# design.net
KiCad netlist of a schematic drawn in EasyEDA Pro
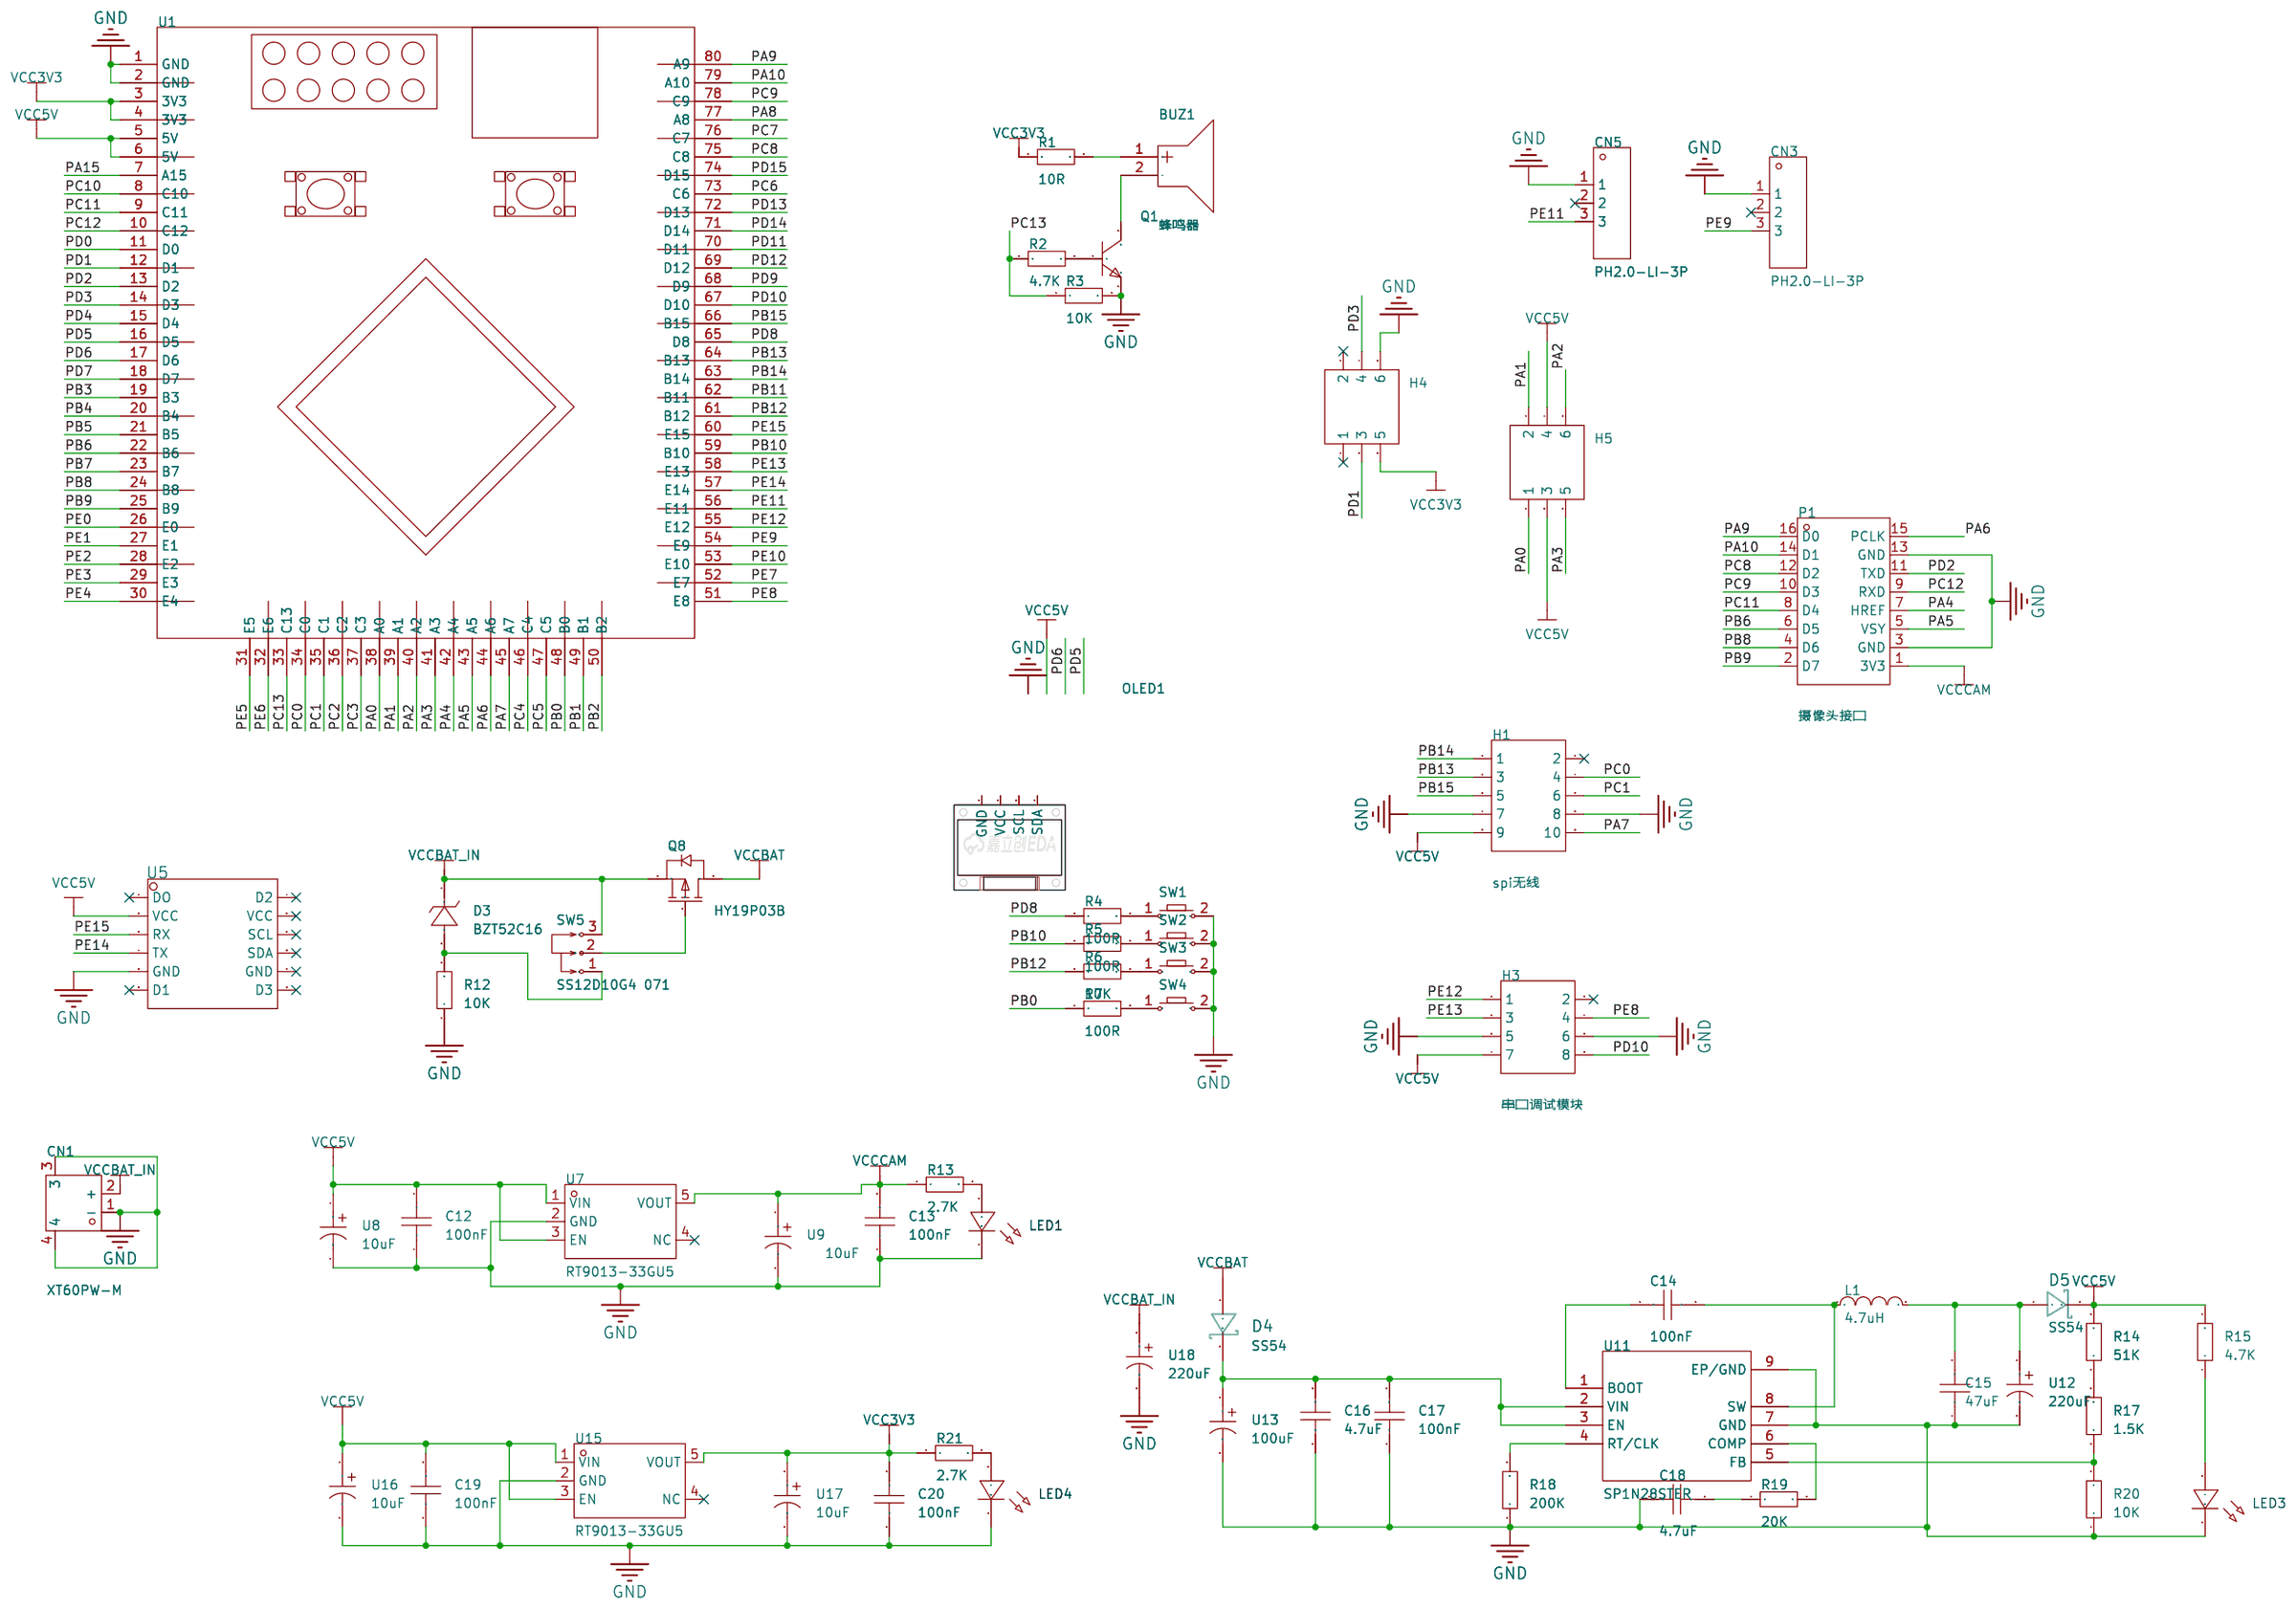
[diagram p0: schematic sheet]

(export (version "E")
  (design (tool "Eeschema 10.0.6"))
  (components
    (comp (ref "BUZ1")
      (value "蜂鸣器")
      (footprint "easyedapro:BUZ-TH_BD9.0-P5.00-D0.6-FD")
      (libsource (lib "easyedapro") (part "蜂鸣器"))
    )
    (comp (ref "C12")
      (value "100nF")
      (footprint "easyedapro:C0603")
      (libsource (lib "easyedapro") (part "CapAcitance"))
    )
    (comp (ref "C13")
      (value "100nF")
      (footprint "easyedapro:C0603")
      (libsource (lib "easyedapro") (part "CapAcitance"))
    )
    (comp (ref "C14")
      (value "100nF")
      (footprint "easyedapro:C0603")
      (libsource (lib "easyedapro") (part "CapAcitance"))
    )
    (comp (ref "C15")
      (value "47uF")
      (footprint "easyedapro:C0603")
      (libsource (lib "easyedapro") (part "CapAcitance"))
    )
    (comp (ref "C16")
      (value "4.7uF")
      (footprint "easyedapro:C0603")
      (libsource (lib "easyedapro") (part "CapAcitance"))
    )
    (comp (ref "C17")
      (value "100nF")
      (footprint "easyedapro:C0603")
      (libsource (lib "easyedapro") (part "CapAcitance"))
    )
    (comp (ref "C18")
      (value "4.7uF")
      (footprint "easyedapro:C0603")
      (libsource (lib "easyedapro") (part "CapAcitance"))
    )
    (comp (ref "C19")
      (value "100nF")
      (footprint "easyedapro:C0603")
      (libsource (lib "easyedapro") (part "CapAcitance"))
    )
    (comp (ref "C20")
      (value "100nF")
      (footprint "easyedapro:C0603")
      (libsource (lib "easyedapro") (part "CapAcitance"))
    )
    (comp (ref "CN1")
      (value "XT60PW-M")
      (footprint "easyedapro:CONN-TH_XT60PW-M")
      (description "类别:-;类型1:-;")
      (fields (field (name "Manufacturer") "AMASS(艾迈斯)"))
      (libsource (lib "easyedapro") (part "XT60PW-M"))
    )
    (comp (ref "CN3")
      (value "PH2.0-LI-3P")
      (footprint "easyedapro:CONN-TH_3P-P2.00_HX20007-3A")
      (libsource (lib "easyedapro") (part "PH2.0-LI-3P"))
    )
    (comp (ref "CN5")
      (value "PH2.0-LI-3P")
      (footprint "easyedapro:CONN-TH_3P-P2.00_HX20007-3A")
      (libsource (lib "easyedapro") (part "PH2.0-LI-3P"))
    )
    (comp (ref "D3")
      (value "BZT52C16")
      (footprint "easyedapro:SOD-123_L2.7-W1.6-LS3.7-RD")
      (description "稳压值(标称值):-;功率:500mW;精度:-;")
      (fields (field (name "Manufacturer") "Slkor(萨科微)"))
      (libsource (lib "easyedapro") (part "BZT52C16_C707145"))
    )
    (comp (ref "D4")
      (value "SS54")
      (footprint "easyedapro:SMA_L4.4-W2.8-LS5.4-R-RD")
      (fields (field (name "Manufacturer") "MDD"))
      (libsource (lib "easyedapro") (part "SS54"))
    )
    (comp (ref "D5")
      (value "SS54")
      (footprint "easyedapro:SMA_L4.4-W2.8-LS5.4-R-RD")
      (fields (field (name "Manufacturer") "MDD"))
      (libsource (lib "easyedapro") (part "SS54"))
    )
    (comp (ref "H1")
      (value "spi无线")
      (footprint "easyedapro:HDR-TH_10P-P2.54-V-F-R2-C5-S2.54")
      (libsource (lib "easyedapro") (part "HDR-F-2.54_2x5"))
    )
    (comp (ref "H3")
      (value "串口调试模块")
      (footprint "easyedapro:HDR-TH_8P-P2.54-V-F-R2-C4-S2.54-1")
      (libsource (lib "easyedapro") (part "HDR-F-2.54_2x4"))
    )
    (comp (ref "H4")
      (value "~")
      (footprint "easyedapro:HDR-TH_6P-P2.54-V-F-R2-C3-S2.54")
      (libsource (lib "easyedapro") (part "HDR-F-2.54_2x3"))
    )
    (comp (ref "H5")
      (value "~")
      (footprint "easyedapro:HDR-TH_6P-P2.54-V-F-R2-C3-S2.54")
      (libsource (lib "easyedapro") (part "HDR-F-2.54_2x3"))
    )
    (comp (ref "L1")
      (value "4.7uH")
      (footprint "easyedapro:L0603")
      (libsource (lib "easyedapro") (part "SDFL1608S100KTF"))
    )
    (comp (ref "LED1")
      (value "~")
      (footprint "easyedapro:LED_0603")
      (libsource (lib "easyedapro") (part "LED_G"))
    )
    (comp (ref "LED3")
      (value "~")
      (footprint "easyedapro:LED_0603")
      (libsource (lib "easyedapro") (part "LED_G"))
    )
    (comp (ref "LED4")
      (value "~")
      (footprint "easyedapro:LED_0603")
      (libsource (lib "easyedapro") (part "LED_G"))
    )
    (comp (ref "OLED1")
      (value "~")
      (footprint "easyedapro:0.96OLED_4P")
      (libsource (lib "easyedapro") (part "0.96OLED模块_4P"))
    )
    (comp (ref "P1")
      (value "摄像头接口")
      (footprint "easyedapro:总钻风摄像头接口")
      (libsource (lib "easyedapro") (part "总钻风"))
    )
    (comp (ref "Q1")
      (value "~")
      (footprint "easyedapro:S8050_SOT-23")
      (libsource (lib "easyedapro") (part "NPN"))
    )
    (comp (ref "Q8")
      (value "HY19P03B")
      (footprint "easyedapro:TO-263-2_L10.2-W8.7-P5.08-LS15.1-BR")
      (fields (field (name "Manufacturer") "HUAYI(华羿微)"))
      (libsource (lib "easyedapro") (part "HY19P03B_C410273"))
    )
    (comp (ref "R1") (value "10R") (footprint "easyedapro:R0603") (libsource (lib "easyedapro") (part "电阻")))
    (comp (ref "R2") (value "4.7K") (footprint "easyedapro:R0603") (libsource (lib "easyedapro") (part "电阻")))
    (comp (ref "R3") (value "10K") (footprint "easyedapro:R0603") (libsource (lib "easyedapro") (part "电阻")))
    (comp (ref "R4") (value "10K") (footprint "easyedapro:R0603") (libsource (lib "easyedapro") (part "电阻")))
    (comp (ref "R5") (value "10K") (footprint "easyedapro:R0603") (libsource (lib "easyedapro") (part "电阻")))
    (comp (ref "R6") (value "10K") (footprint "easyedapro:R0603") (libsource (lib "easyedapro") (part "电阻")))
    (comp (ref "R7") (value "10K") (footprint "easyedapro:R0603") (libsource (lib "easyedapro") (part "电阻")))
    (comp (ref "R12") (value "10K") (footprint "easyedapro:R0603") (libsource (lib "easyedapro") (part "电阻")))
    (comp (ref "R13")
      (value "2.7K")
      (footprint "easyedapro:R0603")
      (libsource (lib "easyedapro") (part "电阻"))
    )
    (comp (ref "R14") (value "51K") (footprint "easyedapro:R0603") (libsource (lib "easyedapro") (part "电阻")))
    (comp (ref "R15")
      (value "4.7K")
      (footprint "easyedapro:R0603")
      (libsource (lib "easyedapro") (part "电阻"))
    )
    (comp (ref "R17")
      (value "1.5K")
      (footprint "easyedapro:R0603")
      (libsource (lib "easyedapro") (part "电阻"))
    )
    (comp (ref "R18")
      (value "200K")
      (footprint "easyedapro:R0603")
      (libsource (lib "easyedapro") (part "电阻"))
    )
    (comp (ref "R19") (value "20K") (footprint "easyedapro:R0603") (libsource (lib "easyedapro") (part "电阻")))
    (comp (ref "R20") (value "10K") (footprint "easyedapro:R0603") (libsource (lib "easyedapro") (part "电阻")))
    (comp (ref "R21")
      (value "2.7K")
      (footprint "easyedapro:R0603")
      (libsource (lib "easyedapro") (part "电阻"))
    )
    (comp (ref "SW1")
      (value "~")
      (footprint "easyedapro:Key_SMD_3x4x2")
      (libsource (lib "easyedapro") (part "轻触按键x2"))
    )
    (comp (ref "SW2")
      (value "~")
      (footprint "easyedapro:Key_SMD_3x4x2")
      (libsource (lib "easyedapro") (part "轻触按键x2"))
    )
    (comp (ref "SW3")
      (value "~")
      (footprint "easyedapro:Key_SMD_3x4x2")
      (libsource (lib "easyedapro") (part "轻触按键x2"))
    )
    (comp (ref "SW4")
      (value "~")
      (footprint "easyedapro:Key_SMD_3x4x2")
      (libsource (lib "easyedapro") (part "轻触按键x2"))
    )
    (comp (ref "SW5")
      (value "SS12D10G4 071")
      (footprint "easyedapro:SW-TH_SHOU-HAN_SS12D10G4")
      (description "电路结构:单刀双掷;安装方式:直插;开关颜色:-;额定电流(DC):2A;额定电压(DC):125V;额定电流(AC):-;额定电压(AC):-;机械寿命:3千次;")
      (fields (field (name "Manufacturer") "SHOU HAN(首韩)"))
      (libsource (lib "easyedapro") (part "SS12D10G4 071"))
    )
    (comp (ref "U1")
      (value "~")
      (footprint "easyedapro:CH32V307VCT6核心板")
      (libsource (lib "easyedapro") (part "CH32V307VCT6"))
    )
    (comp (ref "U5")
      (value "~")
      (footprint "easyedapro:维特智能JY901S")
      (description "9轴姿态角度传感器")
      (libsource (lib "easyedapro") (part "维特智能JY901S"))
    )
    (comp (ref "U7")
      (value "RT9013-33GU5")
      (footprint "easyedapro:SC-70-5_L2.0-W1.3-P0.65-LS2.1-BR")
      (description "输出类型:固定;最大输入电压:5.5V;输出电压:3.3V;最大输出电流:500mA;电源纹波抑制比(PSRR):50dB@(10kHz);输出极性:正极;")
      (fields (field (name "Manufacturer") "RICHTEK(立锜)"))
      (libsource (lib "easyedapro") (part "RT9013-33GU5"))
    )
    (comp (ref "U8")
      (value "10uF")
      (footprint "easyedapro:CAP-SMD_L7.3-W4.3-FD")
      (description "容值:470uF;精度:±20%;额定电压:10V;等效串联电阻:50mΩ@100kHZ;")
      (fields
        (field (name "Manufacturer Part") "TPSE477M010R0050")
        (field (name "Manufacturer") "Kyocera AVX")
      )
      (libsource (lib "easyedapro") (part "TPSE477M010R0050"))
    )
    (comp (ref "U9")
      (value "10uF")
      (footprint "easyedapro:CAP-SMD_L7.3-W4.3-FD")
      (description "容值:470uF;精度:±20%;额定电压:10V;等效串联电阻:50mΩ@100kHZ;")
      (fields
        (field (name "Manufacturer Part") "TPSE477M010R0050")
        (field (name "Manufacturer") "Kyocera AVX")
      )
      (libsource (lib "easyedapro") (part "TPSE477M010R0050"))
    )
    (comp (ref "U11")
      (value "SP1N28STER")
      (footprint "easyedapro:ESOP-8_L4.9-W3.9-P1.27-LS6.0-TL-EP")
      (fields (field (name "Manufacturer Part") "TPS5430DDAR") (field (name "Manufacturer") "TI(德州仪器)"))
      (libsource (lib "easyedapro") (part "SP1N28STER"))
    )
    (comp (ref "U12")
      (value "220uF")
      (footprint "easyedapro:CAP-SMD_L7.3-W4.3-FD")
      (description "容值:470uF;精度:±20%;额定电压:10V;等效串联电阻:50mΩ@100kHZ;")
      (fields
        (field (name "Manufacturer Part") "TPSE477M010R0050")
        (field (name "Manufacturer") "Kyocera AVX")
      )
      (libsource (lib "easyedapro") (part "TPSE477M010R0050"))
    )
    (comp (ref "U13")
      (value "100uF")
      (footprint "easyedapro:CAP-SMD_L7.3-W4.3-FD")
      (description "容值:470uF;精度:±20%;额定电压:10V;等效串联电阻:50mΩ@100kHZ;")
      (fields
        (field (name "Manufacturer Part") "TPSE477M010R0050")
        (field (name "Manufacturer") "Kyocera AVX")
      )
      (libsource (lib "easyedapro") (part "TPSE477M010R0050"))
    )
    (comp (ref "U15")
      (value "RT9013-33GU5")
      (footprint "easyedapro:SC-70-5_L2.0-W1.3-P0.65-LS2.1-BR")
      (description "输出类型:固定;最大输入电压:5.5V;输出电压:3.3V;最大输出电流:500mA;电源纹波抑制比(PSRR):50dB@(10kHz);输出极性:正极;")
      (fields (field (name "Manufacturer") "RICHTEK(立锜)"))
      (libsource (lib "easyedapro") (part "RT9013-33GU5"))
    )
    (comp (ref "U16")
      (value "10uF")
      (footprint "easyedapro:CAP-SMD_L7.3-W4.3-FD")
      (description "容值:470uF;精度:±20%;额定电压:10V;等效串联电阻:50mΩ@100kHZ;")
      (fields
        (field (name "Manufacturer Part") "TPSE477M010R0050")
        (field (name "Manufacturer") "Kyocera AVX")
      )
      (libsource (lib "easyedapro") (part "TPSE477M010R0050"))
    )
    (comp (ref "U17")
      (value "10uF")
      (footprint "easyedapro:CAP-SMD_L7.3-W4.3-FD")
      (description "容值:470uF;精度:±20%;额定电压:10V;等效串联电阻:50mΩ@100kHZ;")
      (fields
        (field (name "Manufacturer Part") "TPSE477M010R0050")
        (field (name "Manufacturer") "Kyocera AVX")
      )
      (libsource (lib "easyedapro") (part "TPSE477M010R0050"))
    )
    (comp (ref "U18")
      (value "220uF")
      (footprint "easyedapro:CAP-SMD_L7.3-W4.3-FD")
      (description "容值:470uF;精度:±20%;额定电压:10V;等效串联电阻:50mΩ@100kHZ;")
      (fields
        (field (name "Manufacturer Part") "TPSE477M010R0050")
        (field (name "Manufacturer") "Kyocera AVX")
      )
      (libsource (lib "easyedapro") (part "TPSE477M010R0050"))
    )
  )
  (nets
    (net (code "1") (name "/PA0") (class "Default")
      (node (ref "H5") (pin "1") (pinfunction "1_1") (pintype "input"))
      (node (ref "U1") (pin "38") (pinfunction "A0_38") (pintype "input"))
    )
    (net (code "2") (name "/PA1") (class "Default")
      (node (ref "H5") (pin "2") (pinfunction "2_2") (pintype "input"))
      (node (ref "U1") (pin "39") (pinfunction "A1_39") (pintype "input"))
    )
    (net (code "3") (name "/PA2") (class "Default")
      (node (ref "H5") (pin "6") (pinfunction "6_6") (pintype "input"))
      (node (ref "U1") (pin "40") (pinfunction "A2_40") (pintype "input"))
    )
    (net (code "4") (name "/PA3") (class "Default")
      (node (ref "H5") (pin "5") (pinfunction "5_5") (pintype "input"))
      (node (ref "U1") (pin "41") (pinfunction "A3_41") (pintype "input"))
    )
    (net (code "5") (name "/PA4") (class "Default")
      (node (ref "P1") (pin "7") (pinfunction "HREF_7") (pintype "input"))
      (node (ref "U1") (pin "42") (pinfunction "A4_42") (pintype "input"))
    )
    (net (code "6") (name "/PA5") (class "Default")
      (node (ref "P1") (pin "5") (pinfunction "VSY_5") (pintype "input"))
      (node (ref "U1") (pin "43") (pinfunction "A5_43") (pintype "input"))
    )
    (net (code "7") (name "/PA6") (class "Default")
      (node (ref "P1") (pin "15") (pinfunction "PCLK_15") (pintype "input"))
      (node (ref "U1") (pin "44") (pinfunction "A6_44") (pintype "input"))
    )
    (net (code "8") (name "/PA7") (class "Default")
      (node (ref "H1") (pin "10") (pinfunction "10_10") (pintype "input"))
      (node (ref "U1") (pin "45") (pinfunction "A7_45") (pintype "input"))
    )
    (net (code "9") (name "/PA8") (class "Default")
      (node (ref "U1") (pin "77") (pinfunction "A8_77") (pintype "input"))
    )
    (net (code "10") (name "/PA9") (class "Default")
      (node (ref "P1") (pin "16") (pinfunction "D0_16") (pintype "input"))
      (node (ref "U1") (pin "80") (pinfunction "A9_80") (pintype "input"))
    )
    (net (code "11") (name "/PA10") (class "Default")
      (node (ref "P1") (pin "14") (pinfunction "D1_14") (pintype "input"))
      (node (ref "U1") (pin "79") (pinfunction "A10_79") (pintype "input"))
    )
    (net (code "12") (name "/PA15") (class "Default")
      (node (ref "U1") (pin "7") (pinfunction "A15_7") (pintype "input"))
    )
    (net (code "13") (name "/PB0") (class "Default")
      (node (ref "R7") (pin "1") (pinfunction "1_1") (pintype "input"))
      (node (ref "U1") (pin "48") (pinfunction "B0_48") (pintype "input"))
    )
    (net (code "14") (name "/PB1") (class "Default")
      (node (ref "U1") (pin "49") (pinfunction "B1_49") (pintype "input"))
    )
    (net (code "15") (name "/PB2") (class "Default")
      (node (ref "U1") (pin "50") (pinfunction "B2_50") (pintype "input"))
    )
    (net (code "16") (name "/PB3") (class "Default")
      (node (ref "U1") (pin "19") (pinfunction "B3_19") (pintype "input"))
    )
    (net (code "17") (name "/PB4") (class "Default")
      (node (ref "U1") (pin "20") (pinfunction "B4_20") (pintype "input"))
    )
    (net (code "18") (name "/PB5") (class "Default")
      (node (ref "U1") (pin "21") (pinfunction "B5_21") (pintype "input"))
    )
    (net (code "19") (name "/PB6") (class "Default")
      (node (ref "P1") (pin "6") (pinfunction "D5_6") (pintype "input"))
      (node (ref "U1") (pin "22") (pinfunction "B6_22") (pintype "input"))
    )
    (net (code "20") (name "/PB7") (class "Default")
      (node (ref "U1") (pin "23") (pinfunction "B7_23") (pintype "input"))
    )
    (net (code "21") (name "/PB8") (class "Default")
      (node (ref "P1") (pin "4") (pinfunction "D6_4") (pintype "input"))
      (node (ref "U1") (pin "24") (pinfunction "B8_24") (pintype "input"))
    )
    (net (code "22") (name "/PB9") (class "Default")
      (node (ref "P1") (pin "2") (pinfunction "D7_2") (pintype "input"))
      (node (ref "U1") (pin "25") (pinfunction "B9_25") (pintype "input"))
    )
    (net (code "23") (name "/PB10") (class "Default")
      (node (ref "R5") (pin "1") (pinfunction "1_1") (pintype "input"))
      (node (ref "U1") (pin "59") (pinfunction "B10_59") (pintype "input"))
    )
    (net (code "24") (name "/PB11") (class "Default")
      (node (ref "U1") (pin "62") (pinfunction "B11_62") (pintype "input"))
    )
    (net (code "25") (name "/PB12") (class "Default")
      (node (ref "R6") (pin "1") (pinfunction "1_1") (pintype "input"))
      (node (ref "U1") (pin "61") (pinfunction "B12_61") (pintype "input"))
    )
    (net (code "26") (name "/PB13") (class "Default")
      (node (ref "H1") (pin "3") (pinfunction "3_3") (pintype "input"))
      (node (ref "U1") (pin "64") (pinfunction "B13_64") (pintype "input"))
    )
    (net (code "27") (name "/PB14") (class "Default")
      (node (ref "H1") (pin "1") (pinfunction "1_1") (pintype "input"))
      (node (ref "U1") (pin "63") (pinfunction "B14_63") (pintype "input"))
    )
    (net (code "28") (name "/PB15") (class "Default")
      (node (ref "H1") (pin "5") (pinfunction "5_5") (pintype "input"))
      (node (ref "U1") (pin "66") (pinfunction "B15_66") (pintype "input"))
    )
    (net (code "29") (name "/PC0") (class "Default")
      (node (ref "H1") (pin "4") (pinfunction "4_4") (pintype "input"))
      (node (ref "U1") (pin "34") (pinfunction "C0_34") (pintype "input"))
    )
    (net (code "30") (name "/PC1") (class "Default")
      (node (ref "H1") (pin "6") (pinfunction "6_6") (pintype "input"))
      (node (ref "U1") (pin "35") (pinfunction "C1_35") (pintype "input"))
    )
    (net (code "31") (name "/PC2") (class "Default")
      (node (ref "U1") (pin "36") (pinfunction "C2_36") (pintype "input"))
    )
    (net (code "32") (name "/PC3") (class "Default")
      (node (ref "U1") (pin "37") (pinfunction "C3_37") (pintype "input"))
    )
    (net (code "33") (name "/PC4") (class "Default")
      (node (ref "U1") (pin "46") (pinfunction "C4_46") (pintype "input"))
    )
    (net (code "34") (name "/PC5") (class "Default")
      (node (ref "U1") (pin "47") (pinfunction "C5_47") (pintype "input"))
    )
    (net (code "35") (name "/PC6") (class "Default")
      (node (ref "U1") (pin "73") (pinfunction "C6_73") (pintype "input"))
    )
    (net (code "36") (name "/PC7") (class "Default")
      (node (ref "U1") (pin "76") (pinfunction "C7_76") (pintype "input"))
    )
    (net (code "37") (name "/PC8") (class "Default")
      (node (ref "P1") (pin "12") (pinfunction "D2_12") (pintype "input"))
      (node (ref "U1") (pin "75") (pinfunction "C8_75") (pintype "input"))
    )
    (net (code "38") (name "/PC9") (class "Default")
      (node (ref "P1") (pin "10") (pinfunction "D3_10") (pintype "input"))
      (node (ref "U1") (pin "78") (pinfunction "C9_78") (pintype "input"))
    )
    (net (code "39") (name "/PC10") (class "Default")
      (node (ref "U1") (pin "8") (pinfunction "C10_8") (pintype "input"))
    )
    (net (code "40") (name "/PC11") (class "Default")
      (node (ref "P1") (pin "8") (pinfunction "D4_8") (pintype "input"))
      (node (ref "U1") (pin "9") (pinfunction "C11_9") (pintype "input"))
    )
    (net (code "41") (name "/PC12") (class "Default")
      (node (ref "P1") (pin "9") (pinfunction "RXD_9") (pintype "input"))
      (node (ref "U1") (pin "10") (pinfunction "C12_10") (pintype "input"))
    )
    (net (code "42") (name "/PC13") (class "Default")
      (node (ref "R2") (pin "1") (pinfunction "1_1") (pintype "input"))
      (node (ref "R3") (pin "1") (pinfunction "1_1") (pintype "input"))
      (node (ref "U1") (pin "33") (pinfunction "C13_33") (pintype "input"))
    )
    (net (code "43") (name "/PD0") (class "Default")
      (node (ref "U1") (pin "11") (pinfunction "D0_11") (pintype "input"))
    )
    (net (code "44") (name "/PD1") (class "Default")
      (node (ref "H4") (pin "3") (pinfunction "3_3") (pintype "input"))
      (node (ref "U1") (pin "12") (pinfunction "D1_12") (pintype "input"))
    )
    (net (code "45") (name "/PD2") (class "Default")
      (node (ref "P1") (pin "11") (pinfunction "TXD_11") (pintype "input"))
      (node (ref "U1") (pin "13") (pinfunction "D2_13") (pintype "input"))
    )
    (net (code "46") (name "/PD3") (class "Default")
      (node (ref "H4") (pin "4") (pinfunction "4_4") (pintype "input"))
      (node (ref "U1") (pin "14") (pinfunction "D3_14") (pintype "input"))
    )
    (net (code "47") (name "/PD4") (class "Default")
      (node (ref "U1") (pin "15") (pinfunction "D4_15") (pintype "input"))
    )
    (net (code "48") (name "/PD5") (class "Default")
      (node (ref "U1") (pin "16") (pinfunction "D5_16") (pintype "input"))
    )
    (net (code "49") (name "/PD6") (class "Default")
      (node (ref "U1") (pin "17") (pinfunction "D6_17") (pintype "input"))
    )
    (net (code "50") (name "/PD7") (class "Default")
      (node (ref "U1") (pin "18") (pinfunction "D7_18") (pintype "input"))
    )
    (net (code "51") (name "/PD8") (class "Default")
      (node (ref "R4") (pin "1") (pinfunction "1_1") (pintype "input"))
      (node (ref "U1") (pin "65") (pinfunction "D8_65") (pintype "input"))
    )
    (net (code "52") (name "/PD9") (class "Default")
      (node (ref "U1") (pin "68") (pinfunction "D9_68") (pintype "input"))
    )
    (net (code "53") (name "/PD10") (class "Default")
      (node (ref "H3") (pin "8") (pinfunction "8_8") (pintype "input"))
      (node (ref "U1") (pin "67") (pinfunction "D10_67") (pintype "input"))
    )
    (net (code "54") (name "/PD11") (class "Default")
      (node (ref "U1") (pin "70") (pinfunction "D11_70") (pintype "input"))
    )
    (net (code "55") (name "/PD12") (class "Default")
      (node (ref "U1") (pin "69") (pinfunction "D12_69") (pintype "input"))
    )
    (net (code "56") (name "/PD13") (class "Default")
      (node (ref "U1") (pin "72") (pinfunction "D13_72") (pintype "input"))
    )
    (net (code "57") (name "/PD14") (class "Default")
      (node (ref "U1") (pin "71") (pinfunction "D14_71") (pintype "input"))
    )
    (net (code "58") (name "/PD15") (class "Default")
      (node (ref "U1") (pin "74") (pinfunction "D15_74") (pintype "input"))
    )
    (net (code "59") (name "/PE0") (class "Default")
      (node (ref "U1") (pin "26") (pinfunction "E0_26") (pintype "input"))
    )
    (net (code "60") (name "/PE1") (class "Default")
      (node (ref "U1") (pin "27") (pinfunction "E1_27") (pintype "input"))
    )
    (net (code "61") (name "/PE2") (class "Default")
      (node (ref "U1") (pin "28") (pinfunction "E2_28") (pintype "input"))
    )
    (net (code "62") (name "/PE3") (class "Default")
      (node (ref "U1") (pin "29") (pinfunction "E3_29") (pintype "input"))
    )
    (net (code "63") (name "/PE4") (class "Default")
      (node (ref "U1") (pin "30") (pinfunction "E4_30") (pintype "input"))
    )
    (net (code "64") (name "/PE5") (class "Default")
      (node (ref "U1") (pin "31") (pinfunction "E5_31") (pintype "input"))
    )
    (net (code "65") (name "/PE6") (class "Default")
      (node (ref "U1") (pin "32") (pinfunction "E6_32") (pintype "input"))
    )
    (net (code "66") (name "/PE7") (class "Default")
      (node (ref "U1") (pin "52") (pinfunction "E7_52") (pintype "input"))
    )
    (net (code "67") (name "/PE8") (class "Default")
      (node (ref "H3") (pin "4") (pinfunction "4_4") (pintype "input"))
      (node (ref "U1") (pin "51") (pinfunction "E8_51") (pintype "input"))
    )
    (net (code "68") (name "/PE9") (class "Default")
      (node (ref "CN3") (pin "3") (pinfunction "3_3") (pintype "input"))
      (node (ref "U1") (pin "54") (pinfunction "E9_54") (pintype "input"))
    )
    (net (code "69") (name "/PE10") (class "Default")
      (node (ref "U1") (pin "53") (pinfunction "E10_53") (pintype "input"))
    )
    (net (code "70") (name "/PE11") (class "Default")
      (node (ref "CN5") (pin "3") (pinfunction "3_3") (pintype "input"))
      (node (ref "U1") (pin "56") (pinfunction "E11_56") (pintype "input"))
    )
    (net (code "71") (name "/PE12") (class "Default")
      (node (ref "H3") (pin "1") (pinfunction "1_1") (pintype "input"))
      (node (ref "U1") (pin "55") (pinfunction "E12_55") (pintype "input"))
    )
    (net (code "72") (name "/PE13") (class "Default")
      (node (ref "H3") (pin "3") (pinfunction "3_3") (pintype "input"))
      (node (ref "U1") (pin "58") (pinfunction "E13_58") (pintype "input"))
    )
    (net (code "73") (name "/PE14") (class "Default")
      (node (ref "U1") (pin "57") (pinfunction "E14_57") (pintype "input"))
      (node (ref "U5") (pin "4") (pinfunction "TX_4") (pintype "input"))
    )
    (net (code "74") (name "/PE15") (class "Default")
      (node (ref "U1") (pin "60") (pinfunction "E15_60") (pintype "input"))
      (node (ref "U5") (pin "3") (pinfunction "RX_3") (pintype "input"))
    )
    (net (code "75") (name "GND") (class "Default")
      (node (ref "C12") (pin "1") (pinfunction "1_1") (pintype "input"))
      (node (ref "C13") (pin "1") (pinfunction "1_1") (pintype "input"))
      (node (ref "C15") (pin "1") (pinfunction "1_1") (pintype "input"))
      (node (ref "C16") (pin "1") (pinfunction "1_1") (pintype "input"))
      (node (ref "C17") (pin "1") (pinfunction "1_1") (pintype "input"))
      (node (ref "C18") (pin "1") (pinfunction "1_1") (pintype "input"))
      (node (ref "C19") (pin "1") (pinfunction "1_1") (pintype "input"))
      (node (ref "C20") (pin "1") (pinfunction "1_1") (pintype "input"))
      (node (ref "CN1") (pin "1") (pinfunction "-_1") (pintype "unspecified"))
      (node (ref "CN1") (pin "3") (pinfunction "3_3") (pintype "unspecified"))
      (node (ref "CN1") (pin "4") (pinfunction "4_4") (pintype "unspecified"))
      (node (ref "CN3") (pin "1") (pinfunction "1_1") (pintype "input"))
      (node (ref "CN5") (pin "1") (pinfunction "1_1") (pintype "input"))
      (node (ref "H1") (pin "7") (pinfunction "7_7") (pintype "input"))
      (node (ref "H1") (pin "8") (pinfunction "8_8") (pintype "input"))
      (node (ref "H3") (pin "5") (pinfunction "5_5") (pintype "input"))
      (node (ref "H3") (pin "6") (pinfunction "6_6") (pintype "input"))
      (node (ref "H4") (pin "6") (pinfunction "6_6") (pintype "input"))
      (node (ref "LED1") (pin "1") (pinfunction "C_1") (pintype "input"))
      (node (ref "LED3") (pin "1") (pinfunction "C_1") (pintype "input"))
      (node (ref "LED4") (pin "1") (pinfunction "C_1") (pintype "input"))
      (node (ref "P1") (pin "13") (pinfunction "GND_13") (pintype "input"))
      (node (ref "P1") (pin "3") (pinfunction "GND_3") (pintype "input"))
      (node (ref "Q1") (pin "2") (pinfunction "2_2") (pintype "unspecified"))
      (node (ref "R12") (pin "1") (pinfunction "1_1") (pintype "input"))
      (node (ref "R18") (pin "1") (pinfunction "1_1") (pintype "input"))
      (node (ref "R20") (pin "1") (pinfunction "1_1") (pintype "input"))
      (node (ref "R3") (pin "2") (pinfunction "2_2") (pintype "input"))
      (node (ref "SW1") (pin "2") (pinfunction "2_2") (pintype "input"))
      (node (ref "SW2") (pin "2") (pinfunction "2_2") (pintype "input"))
      (node (ref "SW3") (pin "2") (pinfunction "2_2") (pintype "input"))
      (node (ref "SW4") (pin "2") (pinfunction "2_2") (pintype "input"))
      (node (ref "U1") (pin "1") (pinfunction "GND_1") (pintype "input"))
      (node (ref "U1") (pin "2") (pinfunction "GND_2") (pintype "input"))
      (node (ref "U11") (pin "7") (pinfunction "GND_7") (pintype "unspecified"))
      (node (ref "U11") (pin "9") (pinfunction "EP/GND_9") (pintype "unspecified"))
      (node (ref "U12") (pin "2") (pinfunction "2_2") (pintype "input"))
      (node (ref "U13") (pin "2") (pinfunction "2_2") (pintype "input"))
      (node (ref "U15") (pin "2") (pinfunction "GND_2") (pintype "unspecified"))
      (node (ref "U16") (pin "2") (pinfunction "2_2") (pintype "input"))
      (node (ref "U17") (pin "2") (pinfunction "2_2") (pintype "input"))
      (node (ref "U18") (pin "2") (pinfunction "2_2") (pintype "input"))
      (node (ref "U5") (pin "5") (pinfunction "GND_5") (pintype "input"))
      (node (ref "U7") (pin "2") (pinfunction "GND_2") (pintype "unspecified"))
      (node (ref "U8") (pin "2") (pinfunction "2_2") (pintype "input"))
      (node (ref "U9") (pin "2") (pinfunction "2_2") (pintype "input"))
    )
    (net (code "76") (name "Net-(BUZ1-+)") (class "Default")
      (node (ref "BUZ1") (pin "1") (pinfunction "+_1") (pintype "unspecified"))
      (node (ref "R1") (pin "2") (pinfunction "2_2") (pintype "input"))
    )
    (net (code "77") (name "Net-(BUZ1--)") (class "Default")
      (node (ref "BUZ1") (pin "2") (pinfunction "-_2") (pintype "unspecified"))
      (node (ref "Q1") (pin "3") (pinfunction "3_3") (pintype "unspecified"))
    )
    (net (code "78") (name "Net-(C18-Pad2)") (class "Default")
      (node (ref "C18") (pin "2") (pinfunction "2_2") (pintype "input"))
      (node (ref "R19") (pin "1") (pinfunction "1_1") (pintype "input"))
    )
    (net (code "79") (name "Net-(D3-A)") (class "Default")
      (node (ref "D3") (pin "2") (pinfunction "A_2") (pintype "unspecified"))
      (node (ref "R12") (pin "2") (pinfunction "2_2") (pintype "input"))
      (node (ref "SW5") (pin "1") (pinfunction "1_1") (pintype "unspecified"))
    )
    (net (code "80") (name "Net-(D4-K)") (class "Default")
      (node (ref "C16") (pin "2") (pinfunction "2_2") (pintype "input"))
      (node (ref "C17") (pin "2") (pinfunction "2_2") (pintype "input"))
      (node (ref "D4") (pin "2") (pinfunction "K_2") (pintype "input"))
      (node (ref "U11") (pin "2") (pinfunction "VIN_2") (pintype "unspecified"))
      (node (ref "U11") (pin "3") (pinfunction "EN_3") (pintype "unspecified"))
      (node (ref "U13") (pin "1") (pinfunction "1_1") (pintype "input"))
    )
    (net (code "81") (name "Net-(D5-A)") (class "Default")
      (node (ref "C15") (pin "2") (pinfunction "2_2") (pintype "input"))
      (node (ref "D5") (pin "1") (pinfunction "A_1") (pintype "input"))
      (node (ref "L1") (pin "2") (pinfunction "2_2") (pintype "unspecified"))
      (node (ref "U12") (pin "1") (pinfunction "1_1") (pintype "input"))
    )
    (net (code "82") (name "Net-(LED1-A)") (class "Default")
      (node (ref "LED1") (pin "2") (pinfunction "A_2") (pintype "input"))
      (node (ref "R13") (pin "2") (pinfunction "2_2") (pintype "input"))
    )
    (net (code "83") (name "Net-(LED3-A)") (class "Default")
      (node (ref "LED3") (pin "2") (pinfunction "A_2") (pintype "input"))
      (node (ref "R15") (pin "1") (pinfunction "1_1") (pintype "input"))
    )
    (net (code "84") (name "Net-(LED4-A)") (class "Default")
      (node (ref "LED4") (pin "2") (pinfunction "A_2") (pintype "input"))
      (node (ref "R21") (pin "2") (pinfunction "2_2") (pintype "input"))
    )
    (net (code "85") (name "Net-(Q1-Pad1)") (class "Default")
      (node (ref "Q1") (pin "1") (pinfunction "1_1") (pintype "unspecified"))
      (node (ref "R2") (pin "2") (pinfunction "2_2") (pintype "input"))
    )
    (net (code "86") (name "Net-(Q8-G)") (class "Default")
      (node (ref "Q8") (pin "1") (pinfunction "G_1") (pintype "input"))
      (node (ref "SW5") (pin "2") (pinfunction "2_2") (pintype "unspecified"))
    )
    (net (code "87") (name "Net-(R4-Pad2)") (class "Default")
      (node (ref "R4") (pin "2") (pinfunction "2_2") (pintype "input"))
      (node (ref "SW1") (pin "1") (pinfunction "1_1") (pintype "input"))
    )
    (net (code "88") (name "Net-(R5-Pad2)") (class "Default")
      (node (ref "R5") (pin "2") (pinfunction "2_2") (pintype "input"))
      (node (ref "SW2") (pin "1") (pinfunction "1_1") (pintype "input"))
    )
    (net (code "89") (name "Net-(R6-Pad2)") (class "Default")
      (node (ref "R6") (pin "2") (pinfunction "2_2") (pintype "input"))
      (node (ref "SW3") (pin "1") (pinfunction "1_1") (pintype "input"))
    )
    (net (code "90") (name "Net-(R7-Pad2)") (class "Default")
      (node (ref "R7") (pin "2") (pinfunction "2_2") (pintype "input"))
      (node (ref "SW4") (pin "1") (pinfunction "1_1") (pintype "input"))
    )
    (net (code "91") (name "Net-(R14-Pad1)") (class "Default")
      (node (ref "R14") (pin "1") (pinfunction "1_1") (pintype "input"))
      (node (ref "R17") (pin "2") (pinfunction "2_2") (pintype "input"))
    )
    (net (code "92") (name "Net-(U11-BOOT)") (class "Default")
      (node (ref "C14") (pin "1") (pinfunction "1_1") (pintype "input"))
      (node (ref "U11") (pin "1") (pinfunction "BOOT_1") (pintype "unspecified"))
    )
    (net (code "93") (name "Net-(U11-COMP)") (class "Default")
      (node (ref "R19") (pin "2") (pinfunction "2_2") (pintype "input"))
      (node (ref "U11") (pin "6") (pinfunction "COMP_6") (pintype "unspecified"))
    )
    (net (code "94") (name "Net-(U11-FB)") (class "Default")
      (node (ref "R17") (pin "1") (pinfunction "1_1") (pintype "input"))
      (node (ref "R20") (pin "2") (pinfunction "2_2") (pintype "input"))
      (node (ref "U11") (pin "5") (pinfunction "FB_5") (pintype "unspecified"))
    )
    (net (code "95") (name "Net-(U11-RT{slash}CLK)") (class "Default")
      (node (ref "R18") (pin "2") (pinfunction "2_2") (pintype "input"))
      (node (ref "U11") (pin "4") (pinfunction "RT/CLK_4") (pintype "unspecified"))
    )
    (net (code "96") (name "Net-(U11-SW)") (class "Default")
      (node (ref "C14") (pin "2") (pinfunction "2_2") (pintype "input"))
      (node (ref "L1") (pin "1") (pinfunction "1_1") (pintype "unspecified"))
      (node (ref "U11") (pin "8") (pinfunction "SW_8") (pintype "unspecified"))
    )
    (net (code "97") (name "VCC3V3") (class "Default")
      (node (ref "C20") (pin "2") (pinfunction "2_2") (pintype "input"))
      (node (ref "H4") (pin "5") (pinfunction "5_5") (pintype "input"))
      (node (ref "R1") (pin "1") (pinfunction "1_1") (pintype "input"))
      (node (ref "R21") (pin "1") (pinfunction "1_1") (pintype "input"))
      (node (ref "U1") (pin "3") (pinfunction "3V3_3") (pintype "input"))
      (node (ref "U1") (pin "4") (pinfunction "3V3_4") (pintype "input"))
      (node (ref "U15") (pin "5") (pinfunction "VOUT_5") (pintype "unspecified"))
      (node (ref "U17") (pin "1") (pinfunction "1_1") (pintype "input"))
    )
    (net (code "98") (name "VCC5V") (class "Default")
      (node (ref "C12") (pin "2") (pinfunction "2_2") (pintype "input"))
      (node (ref "C19") (pin "2") (pinfunction "2_2") (pintype "input"))
      (node (ref "D5") (pin "2") (pinfunction "K_2") (pintype "input"))
      (node (ref "H1") (pin "9") (pinfunction "9_9") (pintype "input"))
      (node (ref "H3") (pin "7") (pinfunction "7_7") (pintype "input"))
      (node (ref "H5") (pin "3") (pinfunction "3_3") (pintype "input"))
      (node (ref "H5") (pin "4") (pinfunction "4_4") (pintype "input"))
      (node (ref "R14") (pin "2") (pinfunction "2_2") (pintype "input"))
      (node (ref "R15") (pin "2") (pinfunction "2_2") (pintype "input"))
      (node (ref "U1") (pin "5") (pinfunction "5V_5") (pintype "input"))
      (node (ref "U1") (pin "6") (pinfunction "5V_6") (pintype "input"))
      (node (ref "U15") (pin "1") (pinfunction "VIN_1") (pintype "unspecified"))
      (node (ref "U15") (pin "3") (pinfunction "EN_3") (pintype "unspecified"))
      (node (ref "U16") (pin "1") (pinfunction "1_1") (pintype "input"))
      (node (ref "U5") (pin "2") (pinfunction "VCC_2") (pintype "input"))
      (node (ref "U7") (pin "1") (pinfunction "VIN_1") (pintype "unspecified"))
      (node (ref "U7") (pin "3") (pinfunction "EN_3") (pintype "unspecified"))
      (node (ref "U8") (pin "1") (pinfunction "1_1") (pintype "input"))
    )
    (net (code "99") (name "VCCBAT") (class "Default")
      (node (ref "D4") (pin "1") (pinfunction "A_1") (pintype "input"))
      (node (ref "Q8") (pin "2") (pinfunction "D_2") (pintype "input"))
    )
    (net (code "100") (name "VCCBAT_IN") (class "Default")
      (node (ref "CN1") (pin "2") (pinfunction "+_2") (pintype "unspecified"))
      (node (ref "D3") (pin "1") (pinfunction "K_1") (pintype "unspecified"))
      (node (ref "Q8") (pin "3") (pinfunction "S_3") (pintype "input"))
      (node (ref "SW5") (pin "3") (pinfunction "3_3") (pintype "unspecified"))
      (node (ref "U18") (pin "1") (pinfunction "1_1") (pintype "input"))
    )
    (net (code "101") (name "VCCCAM") (class "Default")
      (node (ref "C13") (pin "2") (pinfunction "2_2") (pintype "input"))
      (node (ref "P1") (pin "1") (pinfunction "3V3_1") (pintype "input"))
      (node (ref "R13") (pin "1") (pinfunction "1_1") (pintype "input"))
      (node (ref "U7") (pin "5") (pinfunction "VOUT_5") (pintype "unspecified"))
      (node (ref "U9") (pin "1") (pinfunction "1_1") (pintype "input"))
    )
    (net (code "102") (name "unconnected-(CN3-Pad2)") (class "Default")
      (node (ref "CN3") (pin "2") (pinfunction "2_2") (pintype "input+no_connect"))
    )
    (net (code "103") (name "unconnected-(CN5-Pad2)") (class "Default")
      (node (ref "CN5") (pin "2") (pinfunction "2_2") (pintype "input+no_connect"))
    )
    (net (code "104") (name "unconnected-(H1-Pad2)") (class "Default")
      (node (ref "H1") (pin "2") (pinfunction "2_2") (pintype "input+no_connect"))
    )
    (net (code "105") (name "unconnected-(H3-Pad2)") (class "Default")
      (node (ref "H3") (pin "2") (pinfunction "2_2") (pintype "input+no_connect"))
    )
    (net (code "106") (name "unconnected-(H4-Pad1)") (class "Default")
      (node (ref "H4") (pin "1") (pinfunction "1_1") (pintype "input+no_connect"))
    )
    (net (code "107") (name "unconnected-(H4-Pad2)") (class "Default")
      (node (ref "H4") (pin "2") (pinfunction "2_2") (pintype "input+no_connect"))
    )
    (net (code "108") (name "unconnected-(OLED1-GND-Pad1)") (class "Default")
      (node (ref "OLED1") (pin "1") (pinfunction "GND_1") (pintype "input"))
    )
    (net (code "109") (name "unconnected-(OLED1-SCL-Pad3)") (class "Default")
      (node (ref "OLED1") (pin "3") (pinfunction "SCL_3") (pintype "input"))
    )
    (net (code "110") (name "unconnected-(OLED1-SDA-Pad4)") (class "Default")
      (node (ref "OLED1") (pin "4") (pinfunction "SDA_4") (pintype "input"))
    )
    (net (code "111") (name "unconnected-(OLED1-VCC-Pad2)") (class "Default")
      (node (ref "OLED1") (pin "2") (pinfunction "VCC_2") (pintype "input"))
    )
    (net (code "112") (name "unconnected-(U5-D1-Pad6)") (class "Default")
      (node (ref "U5") (pin "6") (pinfunction "D1_6") (pintype "input+no_connect"))
    )
    (net (code "113") (name "unconnected-(U5-D2-Pad7)") (class "Default")
      (node (ref "U5") (pin "7") (pinfunction "D2_7") (pintype "input+no_connect"))
    )
    (net (code "114") (name "unconnected-(U5-D3-Pad12)") (class "Default")
      (node (ref "U5") (pin "12") (pinfunction "D3_12") (pintype "input+no_connect"))
    )
    (net (code "115") (name "unconnected-(U5-DO-Pad1)") (class "Default")
      (node (ref "U5") (pin "1") (pinfunction "DO_1") (pintype "input+no_connect"))
    )
    (net (code "116") (name "unconnected-(U5-GND-Pad11)") (class "Default")
      (node (ref "U5") (pin "11") (pinfunction "GND_11") (pintype "input+no_connect"))
    )
    (net (code "117") (name "unconnected-(U5-SCL-Pad9)") (class "Default")
      (node (ref "U5") (pin "9") (pinfunction "SCL_9") (pintype "input+no_connect"))
    )
    (net (code "118") (name "unconnected-(U5-SDA-Pad10)") (class "Default")
      (node (ref "U5") (pin "10") (pinfunction "SDA_10") (pintype "input+no_connect"))
    )
    (net (code "119") (name "unconnected-(U5-VCC-Pad8)") (class "Default")
      (node (ref "U5") (pin "8") (pinfunction "VCC_8") (pintype "input+no_connect"))
    )
    (net (code "120") (name "unconnected-(U7-NC-Pad4)") (class "Default")
      (node (ref "U7") (pin "4") (pinfunction "NC_4") (pintype "unspecified+no_connect"))
    )
    (net (code "121") (name "unconnected-(U15-NC-Pad4)") (class "Default")
      (node (ref "U15") (pin "4") (pinfunction "NC_4") (pintype "unspecified+no_connect"))
    )
  )
)
